# CAN-to-CAN.net
KiCad netlist of a schematic drawn in Altium Designer
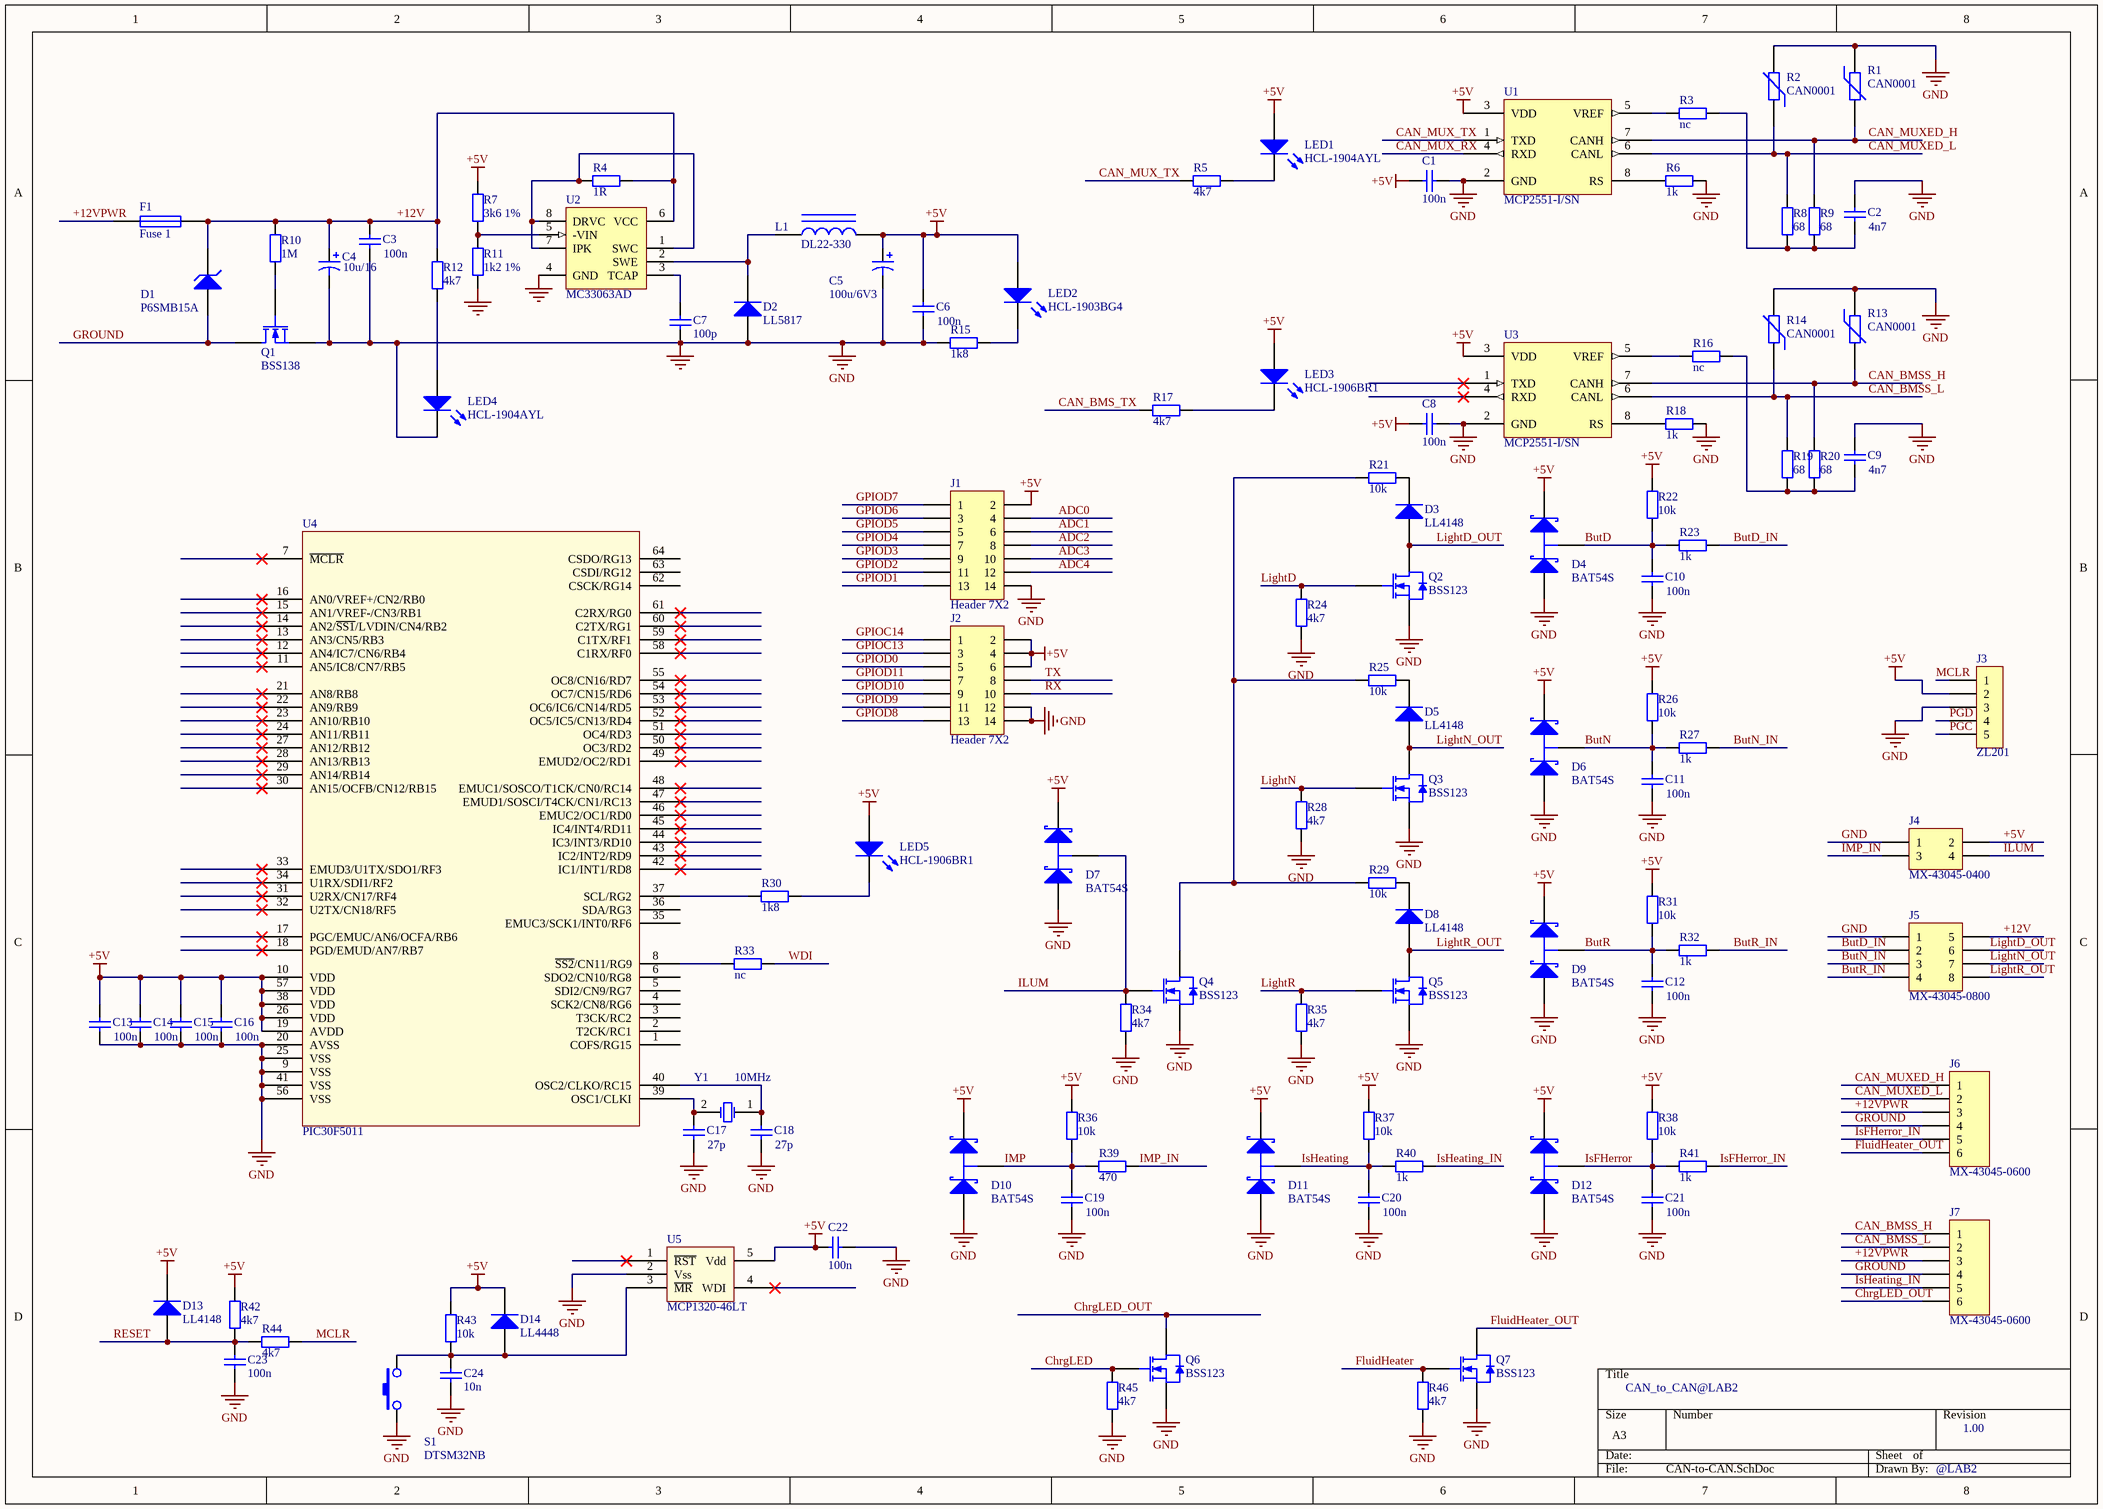
[diagram p0: CAN-to-CAN.SchDoc]

(export (version "E")
  (design (tool "Eeschema 10.0.6"))
  (components
    (comp (ref "C1")
      (value "100n")
      (footprint "0603")
      (description "Capacitor")
      (fields (field (name "PUBLISHER") "Altium Limited"))
      (libsource (lib "Miscellaneous Devices") (part "Cap"))
    )
    (comp (ref "C2")
      (value "4n7")
      (footprint "0603")
      (description "Capacitor")
      (fields (field (name "PUBLISHER") "Altium Limited"))
      (libsource (lib "Miscellaneous Devices") (part "Cap"))
    )
    (comp (ref "C3")
      (value "100n")
      (footprint "0402")
      (description "Capacitor")
      (fields (field (name "PUBLISHER") "Altium Limited"))
      (libsource (lib "Miscellaneous Devices") (part "Cap"))
    )
    (comp (ref "C4")
      (value "10u/16")
      (footprint "0402")
      (description "Polarized Capacitor (Radial)")
      (fields (field (name "PUBLISHER") "Altium Limited"))
      (libsource (lib "Miscellaneous Devices") (part "Cap Pol1"))
    )
    (comp (ref "C5")
      (value "100u/6V3")
      (footprint "0402")
      (description "Polarized Capacitor (Radial)")
      (fields (field (name "PUBLISHER") "Altium Limited"))
      (libsource (lib "Miscellaneous Devices") (part "Cap Pol1"))
    )
    (comp (ref "C6")
      (value "100n")
      (footprint "0603")
      (description "Capacitor")
      (fields (field (name "PUBLISHER") "Altium Limited"))
      (libsource (lib "Miscellaneous Devices") (part "Cap"))
    )
    (comp (ref "C7")
      (value "100p")
      (footprint "0603")
      (description "Capacitor")
      (fields (field (name "PUBLISHER") "Altium Limited"))
      (libsource (lib "Miscellaneous Devices") (part "Cap"))
    )
    (comp (ref "C8")
      (value "100n")
      (footprint "0603")
      (description "Capacitor")
      (fields (field (name "PUBLISHER") "Altium Limited"))
      (libsource (lib "Miscellaneous Devices") (part "Cap"))
    )
    (comp (ref "C9")
      (value "4n7")
      (footprint "0603")
      (description "Capacitor")
      (fields (field (name "PUBLISHER") "Altium Limited"))
      (libsource (lib "Miscellaneous Devices") (part "Cap"))
    )
    (comp (ref "C10")
      (value "100n")
      (footprint "0603")
      (description "Capacitor")
      (fields (field (name "PUBLISHER") "Altium Limited"))
      (libsource (lib "Miscellaneous Devices") (part "Cap"))
    )
    (comp (ref "C11")
      (value "100n")
      (footprint "0603")
      (description "Capacitor")
      (fields (field (name "PUBLISHER") "Altium Limited"))
      (libsource (lib "Miscellaneous Devices") (part "Cap"))
    )
    (comp (ref "C12")
      (value "100n")
      (footprint "0603")
      (description "Capacitor")
      (fields (field (name "PUBLISHER") "Altium Limited"))
      (libsource (lib "Miscellaneous Devices") (part "Cap"))
    )
    (comp (ref "C13")
      (value "100n")
      (footprint "0603")
      (description "Capacitor")
      (fields (field (name "PUBLISHER") "Altium Limited"))
      (libsource (lib "Miscellaneous Devices") (part "Cap"))
    )
    (comp (ref "C14")
      (value "100n")
      (footprint "0603")
      (description "Capacitor")
      (fields (field (name "PUBLISHER") "Altium Limited"))
      (libsource (lib "Miscellaneous Devices") (part "Cap"))
    )
    (comp (ref "C15")
      (value "100n")
      (footprint "0603")
      (description "Capacitor")
      (fields (field (name "PUBLISHER") "Altium Limited"))
      (libsource (lib "Miscellaneous Devices") (part "Cap"))
    )
    (comp (ref "C16")
      (value "100n")
      (footprint "0603")
      (description "Capacitor")
      (fields (field (name "PUBLISHER") "Altium Limited"))
      (libsource (lib "Miscellaneous Devices") (part "Cap"))
    )
    (comp (ref "C17")
      (value "27p")
      (footprint "0603")
      (description "Capacitor")
      (fields (field (name "PUBLISHER") "Altium Limited"))
      (libsource (lib "Miscellaneous Devices") (part "Cap"))
    )
    (comp (ref "C18")
      (value "27p")
      (footprint "0603")
      (description "Capacitor")
      (fields (field (name "PUBLISHER") "Altium Limited"))
      (libsource (lib "Miscellaneous Devices") (part "Cap"))
    )
    (comp (ref "C19")
      (value "100n")
      (footprint "0603")
      (description "Capacitor")
      (fields (field (name "PUBLISHER") "Altium Limited"))
      (libsource (lib "Miscellaneous Devices") (part "Cap"))
    )
    (comp (ref "C20")
      (value "100n")
      (footprint "0603")
      (description "Capacitor")
      (fields (field (name "PUBLISHER") "Altium Limited"))
      (libsource (lib "Miscellaneous Devices") (part "Cap"))
    )
    (comp (ref "C21")
      (value "100n")
      (footprint "0603")
      (description "Capacitor")
      (fields (field (name "PUBLISHER") "Altium Limited"))
      (libsource (lib "Miscellaneous Devices") (part "Cap"))
    )
    (comp (ref "C22")
      (value "100n")
      (footprint "0603")
      (description "Capacitor")
      (fields (field (name "PUBLISHER") "Altium Limited"))
      (libsource (lib "Miscellaneous Devices") (part "Cap"))
    )
    (comp (ref "C23")
      (value "100n")
      (footprint "0603")
      (description "Capacitor")
      (fields (field (name "PUBLISHER") "Altium Limited"))
      (libsource (lib "Miscellaneous Devices") (part "Cap"))
    )
    (comp (ref "C24")
      (value "10n")
      (footprint "0603")
      (description "Capacitor")
      (fields (field (name "PUBLISHER") "Altium Limited"))
      (libsource (lib "Miscellaneous Devices") (part "Cap"))
    )
    (comp (ref "D1")
      (value "P6SMB15A")
      (footprint "SMB")
      (description "Zener Diode")
      (fields (field (name "PUBLISHER") "Altium Limited"))
      (libsource (lib "Miscellaneous Devices") (part "D Zener"))
    )
    (comp (ref "D2")
      (value "LL5817")
      (footprint "DIODE_SMC")
      (description "High Conductance Fast Diode")
      (fields (field (name "PUBLISHER") "Altium Limited"))
      (libsource (lib "FSC Discrete Diode") (part "1N4148"))
    )
    (comp (ref "D3")
      (value "LL4148")
      (footprint "DIODE_SMC")
      (description "High Conductance Fast Diode")
      (fields (field (name "PUBLISHER") "Altium Limited"))
      (libsource (lib "FSC Discrete Diode") (part "1N4148"))
    )
    (comp (ref "D4")
      (value "BAT54S")
      (footprint "SOT-23_M")
      (description "Schottky Barrier Double Diode")
      (fields (field (name "PUBLISHER") "Altium Limited"))
      (libsource (lib "Philips Discrete Diode - Schottky") (part "BAT54S"))
    )
    (comp (ref "D5")
      (value "LL4148")
      (footprint "DIODE_SMC")
      (description "High Conductance Fast Diode")
      (fields (field (name "PUBLISHER") "Altium Limited"))
      (libsource (lib "FSC Discrete Diode") (part "1N4148"))
    )
    (comp (ref "D6")
      (value "BAT54S")
      (footprint "SOT23_M")
      (description "Schottky Barrier Double Diode")
      (fields (field (name "PUBLISHER") "Altium Limited"))
      (libsource (lib "Philips Discrete Diode - Schottky") (part "BAT54S"))
    )
    (comp (ref "D7")
      (value "BAT54S")
      (footprint "SOT23_M")
      (description "Schottky Barrier Double Diode")
      (fields (field (name "PUBLISHER") "Altium Limited"))
      (libsource (lib "Philips Discrete Diode - Schottky") (part "BAT54S"))
    )
    (comp (ref "D8")
      (value "LL4148")
      (footprint "DIODE_SMC")
      (description "High Conductance Fast Diode")
      (fields (field (name "PUBLISHER") "Altium Limited"))
      (libsource (lib "FSC Discrete Diode") (part "1N4148"))
    )
    (comp (ref "D9")
      (value "BAT54S")
      (footprint "SOT23_M")
      (description "Schottky Barrier Double Diode")
      (fields (field (name "PUBLISHER") "Altium Limited"))
      (libsource (lib "Philips Discrete Diode - Schottky") (part "BAT54S"))
    )
    (comp (ref "D10")
      (value "BAT54S")
      (footprint "SOT23_M")
      (description "Schottky Barrier Double Diode")
      (fields (field (name "PUBLISHER") "Altium Limited"))
      (libsource (lib "Philips Discrete Diode - Schottky") (part "BAT54S"))
    )
    (comp (ref "D11")
      (value "BAT54S")
      (footprint "SOT23_M")
      (description "Schottky Barrier Double Diode")
      (fields (field (name "PUBLISHER") "Altium Limited"))
      (libsource (lib "Philips Discrete Diode - Schottky") (part "BAT54S"))
    )
    (comp (ref "D12")
      (value "BAT54S")
      (footprint "SOT23_M")
      (description "Schottky Barrier Double Diode")
      (fields (field (name "PUBLISHER") "Altium Limited"))
      (libsource (lib "Philips Discrete Diode - Schottky") (part "BAT54S"))
    )
    (comp (ref "D13")
      (value "LL4148")
      (footprint "DIODE_SMC")
      (description "High Conductance Fast Diode")
      (fields (field (name "PUBLISHER") "Altium Limited"))
      (libsource (lib "FSC Discrete Diode") (part "1N4148"))
    )
    (comp (ref "D14")
      (value "LL4448")
      (footprint "DIODE_SMC")
      (description "Default Diode")
      (fields (field (name "PUBLISHER") "Altium Limited"))
      (libsource (lib "Miscellaneous Devices") (part "Diode"))
    )
    (comp (ref "F1")
      (value "Fuse 1")
      (footprint "1812")
      (description "Fuse")
      (fields (field (name "PUBLISHER") "Altium Limited"))
      (libsource (lib "Miscellaneous Devices") (part "Fuse 1"))
    )
    (comp (ref "J1")
      (value "Header 7X2")
      (footprint "HDR2X7")
      (description "Header, 7-Pin, Dual row")
      (fields (field (name "PUBLISHER") "Altium Limited"))
      (libsource (lib "Miscellaneous Connectors") (part "Header 7X2"))
    )
    (comp (ref "J2")
      (value "Header 7X2")
      (footprint "HDR2X7")
      (description "Header, 7-Pin, Dual row")
      (fields (field (name "PUBLISHER") "Altium Limited"))
      (libsource (lib "Miscellaneous Connectors") (part "Header 7X2"))
    )
    (comp (ref "J3")
      (value "ZL201")
      (footprint "HDR1X5")
      (description "Connector")
      (libsource (lib "*") (part "CON5"))
    )
    (comp (ref "J4")
      (value "MX-43045-0400")
      (footprint "SOT-343_M")
      (description "Header, 2-Pin, Dual row")
      (fields (field (name "PUBLISHER") "Altium Limited"))
      (libsource (lib "Miscellaneous Connectors") (part "Header 2X2"))
    )
    (comp (ref "J5")
      (value "MX-43045-0800")
      (footprint "DB008_M")
      (description "Header, 4-Pin, Dual row")
      (fields (field (name "PUBLISHER") "Altium Limited"))
      (libsource (lib "Miscellaneous Connectors") (part "Header 4X2A"))
    )
    (comp (ref "J6")
      (value "MX-43045-0600")
      (footprint "Miscellaneous Connectors:HDR1X6")
      (description "Header, 6-Pin")
      (fields (field (name "PUBLISHER") "Altium Limited"))
      (libsource (lib "Miscellaneous Connectors") (part "Header 6"))
    )
    (comp (ref "J7")
      (value "MX-43045-0600")
      (footprint "Miscellaneous Connectors:HDR1X6")
      (description "Header, 6-Pin")
      (fields (field (name "PUBLISHER") "Altium Limited"))
      (libsource (lib "Miscellaneous Connectors") (part "Header 6"))
    )
    (comp (ref "L1")
      (value "DL22-330")
      (footprint "INDC1608L")
      (description "Magnetic-Core Inductor")
      (fields (field (name "PUBLISHER") "Altium Limited"))
      (libsource (lib "Miscellaneous Devices") (part "Inductor Iron"))
    )
    (comp (ref "LED1")
      (value "HCL-1904AYL")
      (footprint "0603")
      (description "Typical BLUE SiC LED")
      (fields (field (name "PUBLISHER") "Altium Limited"))
      (libsource (lib "Miscellaneous Devices") (part "LED3"))
    )
    (comp (ref "LED2")
      (value "HCL-1903BG4")
      (footprint "0603")
      (description "Typical BLUE SiC LED")
      (fields (field (name "PUBLISHER") "Altium Limited"))
      (libsource (lib "Miscellaneous Devices") (part "LED3"))
    )
    (comp (ref "LED3")
      (value "HCL-1906BR1")
      (footprint "0603")
      (description "Typical BLUE SiC LED")
      (fields (field (name "PUBLISHER") "Altium Limited"))
      (libsource (lib "Miscellaneous Devices") (part "LED3"))
    )
    (comp (ref "LED4")
      (value "HCL-1904AYL")
      (footprint "0603")
      (description "Typical BLUE SiC LED")
      (fields (field (name "PUBLISHER") "Altium Limited"))
      (libsource (lib "Miscellaneous Devices") (part "LED3"))
    )
    (comp (ref "LED5")
      (value "HCL-1906BR1")
      (footprint "0603")
      (description "Typical BLUE SiC LED")
      (fields (field (name "PUBLISHER") "Altium Limited"))
      (libsource (lib "Miscellaneous Devices") (part "LED3"))
    )
    (comp (ref "Q1")
      (value "BSS138")
      (footprint "SOT23_M")
      (description "N-Channel Enhancement Mode Vertical DMOS FET")
      (fields (field (name "PUBLISHER") "Altium Limited"))
      (libsource (lib "Zetex Discrete MOSFET") (part "BSS138"))
    )
    (comp (ref "Q2")
      (value "BSS123")
      (footprint "SOT23_M")
      (description "N-channel Enhancement Mode Vertical D-MOSFET")
      (fields (field (name "PUBLISHER") "Altium Limited"))
      (libsource (lib "Philips Discrete MOSFET - Low Power") (part "BSS123"))
    )
    (comp (ref "Q3")
      (value "BSS123")
      (footprint "SOT23_M")
      (description "N-channel Enhancement Mode Vertical D-MOSFET")
      (fields (field (name "PUBLISHER") "Altium Limited"))
      (libsource (lib "Philips Discrete MOSFET - Low Power") (part "BSS123"))
    )
    (comp (ref "Q4")
      (value "BSS123")
      (footprint "SOT23_M")
      (description "N-channel Enhancement Mode Vertical D-MOSFET")
      (fields (field (name "PUBLISHER") "Altium Limited"))
      (libsource (lib "Philips Discrete MOSFET - Low Power") (part "BSS123"))
    )
    (comp (ref "Q5")
      (value "BSS123")
      (footprint "SOT23_M")
      (description "N-channel Enhancement Mode Vertical D-MOSFET")
      (fields (field (name "PUBLISHER") "Altium Limited"))
      (libsource (lib "Philips Discrete MOSFET - Low Power") (part "BSS123"))
    )
    (comp (ref "Q6")
      (value "BSS123")
      (footprint "SOT23_M")
      (description "N-channel Enhancement Mode Vertical D-MOSFET")
      (fields (field (name "PUBLISHER") "Altium Limited"))
      (libsource (lib "Philips Discrete MOSFET - Low Power") (part "BSS123"))
    )
    (comp (ref "Q7")
      (value "BSS123")
      (footprint "SOT23_M")
      (description "N-channel Enhancement Mode Vertical D-MOSFET")
      (fields (field (name "PUBLISHER") "Altium Limited"))
      (libsource (lib "Philips Discrete MOSFET - Low Power") (part "BSS123"))
    )
    (comp (ref "R1")
      (value "CAN0001")
      (footprint "0603")
      (description "Varistor (Voltage-Sensitive Resistor)")
      (fields (field (name "PUBLISHER") "Altium Limited"))
      (libsource (lib "Miscellaneous Devices") (part "Res Varistor"))
    )
    (comp (ref "R2")
      (value "CAN0001")
      (footprint "0603")
      (description "Varistor (Voltage-Sensitive Resistor)")
      (fields (field (name "PUBLISHER") "Altium Limited"))
      (libsource (lib "Miscellaneous Devices") (part "Res Varistor"))
    )
    (comp (ref "R3")
      (value "nc")
      (footprint "0603")
      (description "Resistor")
      (fields (field (name "PUBLISHER") "Altium Limited"))
      (libsource (lib "") (part "Res2_2"))
    )
    (comp (ref "R4")
      (value "1R")
      (footprint "12Z-2010")
      (description "Resistor")
      (fields (field (name "PUBLISHER") "Altium Limited"))
      (libsource (lib "") (part "Res2_2"))
    )
    (comp (ref "R5")
      (value "4k7")
      (footprint "0603")
      (description "Resistor")
      (fields (field (name "PUBLISHER") "Altium Limited"))
      (libsource (lib "") (part "Res2_3"))
    )
    (comp (ref "R6")
      (value "1k")
      (footprint "0603")
      (description "Resistor")
      (fields (field (name "PUBLISHER") "Altium Limited"))
      (libsource (lib "") (part "Res2_2"))
    )
    (comp (ref "R7")
      (value "3k6 1%")
      (footprint "0603")
      (description "Resistor")
      (fields (field (name "PUBLISHER") "Altium Limited"))
      (libsource (lib "") (part "Res2_1"))
    )
    (comp (ref "R8")
      (value "68")
      (footprint "0603")
      (description "Resistor")
      (fields (field (name "PUBLISHER") "Altium Limited"))
      (libsource (lib "") (part "Res2_1"))
    )
    (comp (ref "R9")
      (value "68")
      (footprint "0603")
      (description "Resistor")
      (fields (field (name "PUBLISHER") "Altium Limited"))
      (libsource (lib "") (part "Res2_1"))
    )
    (comp (ref "R10")
      (value "1M")
      (footprint "0603")
      (description "Resistor")
      (fields (field (name "PUBLISHER") "Altium Limited"))
      (libsource (lib "") (part "Res2_1"))
    )
    (comp (ref "R11")
      (value "1k2 1%")
      (footprint "0603")
      (description "Resistor")
      (fields (field (name "PUBLISHER") "Altium Limited"))
      (libsource (lib "Miscellaneous Devices") (part "Res2"))
    )
    (comp (ref "R12")
      (value "4k7")
      (footprint "0603")
      (description "Resistor")
      (fields (field (name "PUBLISHER") "Altium Limited"))
      (libsource (lib "") (part "Res2_1"))
    )
    (comp (ref "R13")
      (value "CAN0001")
      (footprint "0603")
      (description "Varistor (Voltage-Sensitive Resistor)")
      (fields (field (name "PUBLISHER") "Altium Limited"))
      (libsource (lib "Miscellaneous Devices") (part "Res Varistor"))
    )
    (comp (ref "R14")
      (value "CAN0001")
      (footprint "0603")
      (description "Varistor (Voltage-Sensitive Resistor)")
      (fields (field (name "PUBLISHER") "Altium Limited"))
      (libsource (lib "Miscellaneous Devices") (part "Res Varistor"))
    )
    (comp (ref "R15")
      (value "1k8")
      (footprint "0603")
      (description "Resistor")
      (fields (field (name "PUBLISHER") "Altium Limited"))
      (libsource (lib "") (part "Res2_3"))
    )
    (comp (ref "R16")
      (value "nc")
      (footprint "0603")
      (description "Resistor")
      (fields (field (name "PUBLISHER") "Altium Limited"))
      (libsource (lib "") (part "Res2_2"))
    )
    (comp (ref "R17")
      (value "4k7")
      (footprint "0603")
      (description "Resistor")
      (fields (field (name "PUBLISHER") "Altium Limited"))
      (libsource (lib "") (part "Res2_3"))
    )
    (comp (ref "R18")
      (value "1k")
      (footprint "0603")
      (description "Resistor")
      (fields (field (name "PUBLISHER") "Altium Limited"))
      (libsource (lib "") (part "Res2_2"))
    )
    (comp (ref "R19")
      (value "68")
      (footprint "0603")
      (description "Resistor")
      (fields (field (name "PUBLISHER") "Altium Limited"))
      (libsource (lib "") (part "Res2_1"))
    )
    (comp (ref "R20")
      (value "68")
      (footprint "0603")
      (description "Resistor")
      (fields (field (name "PUBLISHER") "Altium Limited"))
      (libsource (lib "") (part "Res2_1"))
    )
    (comp (ref "R21")
      (value "10k")
      (footprint "0603")
      (description "Resistor")
      (fields (field (name "PUBLISHER") "Altium Limited"))
      (libsource (lib "") (part "Res2_2"))
    )
    (comp (ref "R22")
      (value "10k")
      (footprint "0603")
      (description "Resistor")
      (fields (field (name "PUBLISHER") "Altium Limited"))
      (libsource (lib "") (part "Res2_1"))
    )
    (comp (ref "R23")
      (value "1k")
      (footprint "0603")
      (description "Resistor")
      (fields (field (name "PUBLISHER") "Altium Limited"))
      (libsource (lib "") (part "Res2_3"))
    )
    (comp (ref "R24")
      (value "4k7")
      (footprint "0603")
      (description "Resistor")
      (fields (field (name "PUBLISHER") "Altium Limited"))
      (libsource (lib "") (part "Res2_1"))
    )
    (comp (ref "R25")
      (value "10k")
      (footprint "0603")
      (description "Resistor")
      (fields (field (name "PUBLISHER") "Altium Limited"))
      (libsource (lib "") (part "Res2_2"))
    )
    (comp (ref "R26")
      (value "10k")
      (footprint "0603")
      (description "Resistor")
      (fields (field (name "PUBLISHER") "Altium Limited"))
      (libsource (lib "") (part "Res2_1"))
    )
    (comp (ref "R27")
      (value "1k")
      (footprint "0603")
      (description "Resistor")
      (fields (field (name "PUBLISHER") "Altium Limited"))
      (libsource (lib "") (part "Res2_3"))
    )
    (comp (ref "R28")
      (value "4k7")
      (footprint "0603")
      (description "Resistor")
      (fields (field (name "PUBLISHER") "Altium Limited"))
      (libsource (lib "") (part "Res2_1"))
    )
    (comp (ref "R29")
      (value "10k")
      (footprint "0603")
      (description "Resistor")
      (fields (field (name "PUBLISHER") "Altium Limited"))
      (libsource (lib "") (part "Res2_2"))
    )
    (comp (ref "R30")
      (value "1k8")
      (footprint "0603")
      (description "Resistor")
      (fields (field (name "PUBLISHER") "Altium Limited"))
      (libsource (lib "") (part "Res2_3"))
    )
    (comp (ref "R31")
      (value "10k")
      (footprint "0603")
      (description "Resistor")
      (fields (field (name "PUBLISHER") "Altium Limited"))
      (libsource (lib "") (part "Res2_1"))
    )
    (comp (ref "R32")
      (value "1k")
      (footprint "0603")
      (description "Resistor")
      (fields (field (name "PUBLISHER") "Altium Limited"))
      (libsource (lib "") (part "Res2_3"))
    )
    (comp (ref "R33")
      (value "nc")
      (footprint "0603")
      (description "Resistor")
      (fields (field (name "PUBLISHER") "Altium Limited"))
      (libsource (lib "") (part "Res2_3"))
    )
    (comp (ref "R34")
      (value "4k7")
      (footprint "0603")
      (description "Resistor")
      (fields (field (name "PUBLISHER") "Altium Limited"))
      (libsource (lib "") (part "Res2_1"))
    )
    (comp (ref "R35")
      (value "4k7")
      (footprint "0603")
      (description "Resistor")
      (fields (field (name "PUBLISHER") "Altium Limited"))
      (libsource (lib "") (part "Res2_1"))
    )
    (comp (ref "R36")
      (value "10k")
      (footprint "0603")
      (description "Resistor")
      (fields (field (name "PUBLISHER") "Altium Limited"))
      (libsource (lib "") (part "Res2_1"))
    )
    (comp (ref "R37")
      (value "10k")
      (footprint "0603")
      (description "Resistor")
      (fields (field (name "PUBLISHER") "Altium Limited"))
      (libsource (lib "") (part "Res2_1"))
    )
    (comp (ref "R38")
      (value "10k")
      (footprint "0603")
      (description "Resistor")
      (fields (field (name "PUBLISHER") "Altium Limited"))
      (libsource (lib "") (part "Res2_1"))
    )
    (comp (ref "R39")
      (value "470")
      (footprint "0603")
      (description "Resistor")
      (fields (field (name "PUBLISHER") "Altium Limited"))
      (libsource (lib "") (part "Res2_3"))
    )
    (comp (ref "R40")
      (value "1k")
      (footprint "0603")
      (description "Resistor")
      (fields (field (name "PUBLISHER") "Altium Limited"))
      (libsource (lib "") (part "Res2_3"))
    )
    (comp (ref "R41")
      (value "1k")
      (footprint "0603")
      (description "Resistor")
      (fields (field (name "PUBLISHER") "Altium Limited"))
      (libsource (lib "") (part "Res2_3"))
    )
    (comp (ref "R42")
      (value "4k7")
      (footprint "0603")
      (description "Resistor")
      (fields (field (name "PUBLISHER") "Altium Limited"))
      (libsource (lib "") (part "Res2_1"))
    )
    (comp (ref "R43")
      (value "10k")
      (footprint "0603")
      (description "Resistor")
      (fields (field (name "PUBLISHER") "Altium Limited"))
      (libsource (lib "Miscellaneous Devices") (part "Res2"))
    )
    (comp (ref "R44")
      (value "4k7")
      (footprint "0603")
      (description "Resistor")
      (fields (field (name "PUBLISHER") "Altium Limited"))
      (libsource (lib "") (part "Res2_3"))
    )
    (comp (ref "R45")
      (value "4k7")
      (footprint "0603")
      (description "Resistor")
      (fields (field (name "PUBLISHER") "Altium Limited"))
      (libsource (lib "") (part "Res2_1"))
    )
    (comp (ref "R46")
      (value "4k7")
      (footprint "0603")
      (description "Resistor")
      (fields (field (name "PUBLISHER") "Altium Limited"))
      (libsource (lib "") (part "Res2_1"))
    )
    (comp (ref "S1")
      (value "DTSM32NB")
      (footprint "SPST-2")
      (description "Switch PushButton")
      (libsource (lib "*") (part "PUSHB"))
    )
    (comp (ref "U1")
      (value "MCP2551-I/SN")
      (footprint "DB008_M")
      (description "High Speed CAN Transceiver, 8-Pin Plastic SOIC, Industrial Grade")
      (fields (field (name "PUBLISHER") "Altium Limited"))
      (libsource (lib "Microchip Interface Line Transceiver") (part "MCP2551-I/SN"))
    )
    (comp (ref "U2")
      (value "MC33063AD")
      (footprint "SO8_N")
      (description "DC-to-DC Converter Control Circuit")
      (fields (field (name "PUBLISHER") "Altium Limited"))
      (libsource (lib "Motorola Power Mgt DC-DC Converter") (part "MC33063AD"))
    )
    (comp (ref "U3")
      (value "MCP2551-I/SN")
      (footprint "SO8_N")
      (description "High Speed CAN Transceiver, 8-Pin Plastic SOIC, Industrial Grade")
      (fields (field (name "PUBLISHER") "Altium Limited"))
      (libsource (lib "Microchip Interface Line Transceiver") (part "MCP2551-I/SN"))
    )
    (comp (ref "U4")
      (value "PIC30F5011")
      (footprint "ST-64-2_M")
      (description "PIC30F5011 - Up")
      (libsource (lib "X-Tro's Misc") (part "PIC30F5011"))
    )
    (comp (ref "U5")
      (value "MCP1320-46LT")
      (footprint "SOT23-5")
      (libsource (lib "X-Tro's Misc") (part "MCP1320"))
    )
    (comp (ref "Y1")
      (value "10MHz")
      (footprint "XTALSMD2")
      (description "Crystal Oscillator")
      (fields (field (name "PUBLISHER") "Altium Limited"))
      (libsource (lib "Miscellaneous Devices") (part "XTAL"))
    )
  )
  (nets
    (net (code "1") (name "+5V") (class "Default")
      (node (ref "C1") (pin "1") (pinfunction "1_1") (pintype "passive"))
      (node (ref "C13") (pin "1") (pinfunction "1_1") (pintype "passive"))
      (node (ref "C14") (pin "1") (pinfunction "1_1") (pintype "passive"))
      (node (ref "C15") (pin "1") (pinfunction "1_1") (pintype "passive"))
      (node (ref "C16") (pin "1") (pinfunction "1_1") (pintype "passive"))
      (node (ref "C22") (pin "1") (pinfunction "1_1") (pintype "passive"))
      (node (ref "C5") (pin "1") (pinfunction "1_1") (pintype "passive"))
      (node (ref "C6") (pin "1") (pinfunction "1_1") (pintype "passive"))
      (node (ref "C8") (pin "1") (pinfunction "1_1") (pintype "passive"))
      (node (ref "D10") (pin "2") (pinfunction "K_2") (pintype "passive"))
      (node (ref "D11") (pin "2") (pinfunction "K_2") (pintype "passive"))
      (node (ref "D12") (pin "2") (pinfunction "K_2") (pintype "passive"))
      (node (ref "D13") (pin "2") (pinfunction "K_2") (pintype "passive"))
      (node (ref "D14") (pin "2") (pinfunction "K_2") (pintype "passive"))
      (node (ref "D4") (pin "2") (pinfunction "K_2") (pintype "passive"))
      (node (ref "D6") (pin "2") (pinfunction "K_2") (pintype "passive"))
      (node (ref "D7") (pin "2") (pinfunction "K_2") (pintype "passive"))
      (node (ref "D9") (pin "2") (pinfunction "K_2") (pintype "passive"))
      (node (ref "J1") (pin "2") (pinfunction "2_2") (pintype "passive"))
      (node (ref "J2") (pin "2") (pinfunction "2_2") (pintype "passive"))
      (node (ref "J2") (pin "4") (pinfunction "4_4") (pintype "passive"))
      (node (ref "J2") (pin "6") (pinfunction "6_6") (pintype "passive"))
      (node (ref "J3") (pin "2") (pinfunction "2_2") (pintype "passive"))
      (node (ref "J4") (pin "2") (pinfunction "2_2") (pintype "passive"))
      (node (ref "L1") (pin "2") (pinfunction "2_2") (pintype "passive"))
      (node (ref "LED1") (pin "1") (pinfunction "A_1") (pintype "passive"))
      (node (ref "LED2") (pin "1") (pinfunction "A_1") (pintype "passive"))
      (node (ref "LED3") (pin "1") (pinfunction "A_1") (pintype "passive"))
      (node (ref "LED5") (pin "1") (pinfunction "A_1") (pintype "passive"))
      (node (ref "R22") (pin "1") (pinfunction "1_1") (pintype "passive"))
      (node (ref "R26") (pin "1") (pinfunction "1_1") (pintype "passive"))
      (node (ref "R31") (pin "1") (pinfunction "1_1") (pintype "passive"))
      (node (ref "R36") (pin "1") (pinfunction "1_1") (pintype "passive"))
      (node (ref "R37") (pin "1") (pinfunction "1_1") (pintype "passive"))
      (node (ref "R38") (pin "1") (pinfunction "1_1") (pintype "passive"))
      (node (ref "R42") (pin "1") (pinfunction "1_1") (pintype "passive"))
      (node (ref "R43") (pin "2") (pinfunction "2_2") (pintype "passive"))
      (node (ref "R7") (pin "1") (pinfunction "1_1") (pintype "passive"))
      (node (ref "U1") (pin "3") (pinfunction "VDD_3") (pintype "power_in"))
      (node (ref "U3") (pin "3") (pinfunction "VDD_3") (pintype "power_in"))
      (node (ref "U4") (pin "10") (pinfunction "VDD_10") (pintype "passive"))
      (node (ref "U4") (pin "19") (pinfunction "AVDD_19") (pintype "passive"))
      (node (ref "U4") (pin "26") (pinfunction "VDD_26") (pintype "passive"))
      (node (ref "U4") (pin "38") (pinfunction "VDD_38") (pintype "passive"))
      (node (ref "U4") (pin "57") (pinfunction "VDD_57") (pintype "passive"))
      (node (ref "U5") (pin "5") (pinfunction "Vdd_5") (pintype "passive"))
    )
    (net (code "2") (name "/+12V") (class "Default")
      (node (ref "C3") (pin "1") (pinfunction "1_1") (pintype "passive"))
      (node (ref "C4") (pin "1") (pinfunction "1_1") (pintype "passive"))
      (node (ref "D1") (pin "2") (pinfunction "K_2") (pintype "passive"))
      (node (ref "F1") (pin "2") (pinfunction "2_2") (pintype "passive"))
      (node (ref "J5") (pin "5") (pinfunction "5_5") (pintype "passive"))
      (node (ref "R10") (pin "1") (pinfunction "1_1") (pintype "passive"))
      (node (ref "R12") (pin "1") (pinfunction "1_1") (pintype "passive"))
      (node (ref "R4") (pin "2") (pinfunction "2_2") (pintype "passive"))
      (node (ref "U2") (pin "6") (pinfunction "VCC_6") (pintype "power_in"))
    )
    (net (code "3") (name "/+12VPWR") (class "Default")
      (node (ref "F1") (pin "1") (pinfunction "1_1") (pintype "passive"))
      (node (ref "J6") (pin "3") (pinfunction "3_3") (pintype "passive"))
      (node (ref "J7") (pin "3") (pinfunction "3_3") (pintype "passive"))
    )
    (net (code "4") (name "/ADC0") (class "Default")
      (node (ref "J1") (pin "4") (pinfunction "4_4") (pintype "passive"))
    )
    (net (code "5") (name "/ADC1") (class "Default")
      (node (ref "J1") (pin "6") (pinfunction "6_6") (pintype "passive"))
    )
    (net (code "6") (name "/ADC2") (class "Default")
      (node (ref "J1") (pin "8") (pinfunction "8_8") (pintype "passive"))
    )
    (net (code "7") (name "/ADC3") (class "Default")
      (node (ref "J1") (pin "10") (pinfunction "10_10") (pintype "passive"))
    )
    (net (code "8") (name "/ADC4") (class "Default")
      (node (ref "J1") (pin "12") (pinfunction "12_12") (pintype "passive"))
    )
    (net (code "9") (name "/ButD") (class "Default")
      (node (ref "C10") (pin "1") (pinfunction "1_1") (pintype "passive"))
      (node (ref "D4") (pin "3") (pinfunction "C_3") (pintype "passive"))
      (node (ref "R22") (pin "2") (pinfunction "2_2") (pintype "passive"))
      (node (ref "R23") (pin "2") (pinfunction "2_2") (pintype "passive"))
    )
    (net (code "10") (name "/ButD_IN") (class "Default")
      (node (ref "J5") (pin "2") (pinfunction "2_2") (pintype "passive"))
      (node (ref "R23") (pin "1") (pinfunction "1_1") (pintype "passive"))
    )
    (net (code "11") (name "/ButN") (class "Default")
      (node (ref "C11") (pin "1") (pinfunction "1_1") (pintype "passive"))
      (node (ref "D6") (pin "3") (pinfunction "C_3") (pintype "passive"))
      (node (ref "R26") (pin "2") (pinfunction "2_2") (pintype "passive"))
      (node (ref "R27") (pin "2") (pinfunction "2_2") (pintype "passive"))
    )
    (net (code "12") (name "/ButN_IN") (class "Default")
      (node (ref "J5") (pin "3") (pinfunction "3_3") (pintype "passive"))
      (node (ref "R27") (pin "1") (pinfunction "1_1") (pintype "passive"))
    )
    (net (code "13") (name "/ButR") (class "Default")
      (node (ref "C12") (pin "1") (pinfunction "1_1") (pintype "passive"))
      (node (ref "D9") (pin "3") (pinfunction "C_3") (pintype "passive"))
      (node (ref "R31") (pin "2") (pinfunction "2_2") (pintype "passive"))
      (node (ref "R32") (pin "2") (pinfunction "2_2") (pintype "passive"))
    )
    (net (code "14") (name "/ButR_IN") (class "Default")
      (node (ref "J5") (pin "4") (pinfunction "4_4") (pintype "passive"))
      (node (ref "R32") (pin "1") (pinfunction "1_1") (pintype "passive"))
    )
    (net (code "15") (name "/CAN_BMSS_H") (class "Default")
      (node (ref "J7") (pin "1") (pinfunction "1_1") (pintype "passive"))
      (node (ref "R13") (pin "2") (pinfunction "2_2") (pintype "passive"))
      (node (ref "R20") (pin "1") (pinfunction "1_1") (pintype "passive"))
      (node (ref "U3") (pin "7") (pinfunction "CANH_7") (pintype "output"))
    )
    (net (code "16") (name "/CAN_BMSS_L") (class "Default")
      (node (ref "J7") (pin "2") (pinfunction "2_2") (pintype "passive"))
      (node (ref "R14") (pin "1") (pinfunction "1_1") (pintype "passive"))
      (node (ref "R19") (pin "1") (pinfunction "1_1") (pintype "passive"))
      (node (ref "U3") (pin "6") (pinfunction "CANL_6") (pintype "output"))
    )
    (net (code "17") (name "/CAN_BMS_TX") (class "Default")
      (node (ref "R17") (pin "2") (pinfunction "2_2") (pintype "passive"))
    )
    (net (code "18") (name "/CAN_MUXED_H") (class "Default")
      (node (ref "J6") (pin "1") (pinfunction "1_1") (pintype "passive"))
      (node (ref "R1") (pin "2") (pinfunction "2_2") (pintype "passive"))
      (node (ref "R9") (pin "1") (pinfunction "1_1") (pintype "passive"))
      (node (ref "U1") (pin "7") (pinfunction "CANH_7") (pintype "output"))
    )
    (net (code "19") (name "/CAN_MUXED_L") (class "Default")
      (node (ref "J6") (pin "2") (pinfunction "2_2") (pintype "passive"))
      (node (ref "R2") (pin "1") (pinfunction "1_1") (pintype "passive"))
      (node (ref "R8") (pin "1") (pinfunction "1_1") (pintype "passive"))
      (node (ref "U1") (pin "6") (pinfunction "CANL_6") (pintype "output"))
    )
    (net (code "20") (name "/CAN_MUX_RX") (class "Default")
      (node (ref "U1") (pin "4") (pinfunction "RXD_4") (pintype "output"))
    )
    (net (code "21") (name "/CAN_MUX_TX") (class "Default")
      (node (ref "R5") (pin "2") (pinfunction "2_2") (pintype "passive"))
      (node (ref "U1") (pin "1") (pinfunction "TXD_1") (pintype "input"))
    )
    (net (code "22") (name "/ChrgLED") (class "Default")
      (node (ref "Q6") (pin "3") (pinfunction "G_3") (pintype "passive"))
      (node (ref "R45") (pin "1") (pinfunction "1_1") (pintype "passive"))
    )
    (net (code "23") (name "/ChrgLED_OUT") (class "Default")
      (node (ref "J7") (pin "6") (pinfunction "6_6") (pintype "passive"))
      (node (ref "Q6") (pin "1") (pinfunction "D_1") (pintype "passive"))
    )
    (net (code "24") (name "/FluidHeater") (class "Default")
      (node (ref "Q7") (pin "3") (pinfunction "G_3") (pintype "passive"))
      (node (ref "R46") (pin "1") (pinfunction "1_1") (pintype "passive"))
    )
    (net (code "25") (name "/FluidHeater_OUT") (class "Default")
      (node (ref "J6") (pin "6") (pinfunction "6_6") (pintype "passive"))
      (node (ref "Q7") (pin "1") (pinfunction "D_1") (pintype "passive"))
    )
    (net (code "26") (name "/GPIOC13") (class "Default")
      (node (ref "J2") (pin "3") (pinfunction "3_3") (pintype "passive"))
    )
    (net (code "27") (name "/GPIOC14") (class "Default")
      (node (ref "J2") (pin "1") (pinfunction "1_1") (pintype "passive"))
    )
    (net (code "28") (name "/GPIOD0") (class "Default")
      (node (ref "J2") (pin "5") (pinfunction "5_5") (pintype "passive"))
    )
    (net (code "29") (name "/GPIOD1") (class "Default")
      (node (ref "J1") (pin "13") (pinfunction "13_13") (pintype "passive"))
    )
    (net (code "30") (name "/GPIOD2") (class "Default")
      (node (ref "J1") (pin "11") (pinfunction "11_11") (pintype "passive"))
    )
    (net (code "31") (name "/GPIOD3") (class "Default")
      (node (ref "J1") (pin "9") (pinfunction "9_9") (pintype "passive"))
    )
    (net (code "32") (name "/GPIOD4") (class "Default")
      (node (ref "J1") (pin "7") (pinfunction "7_7") (pintype "passive"))
    )
    (net (code "33") (name "/GPIOD5") (class "Default")
      (node (ref "J1") (pin "5") (pinfunction "5_5") (pintype "passive"))
    )
    (net (code "34") (name "/GPIOD6") (class "Default")
      (node (ref "J1") (pin "3") (pinfunction "3_3") (pintype "passive"))
    )
    (net (code "35") (name "/GPIOD7") (class "Default")
      (node (ref "J1") (pin "1") (pinfunction "1_1") (pintype "passive"))
    )
    (net (code "36") (name "/GPIOD8") (class "Default")
      (node (ref "J2") (pin "13") (pinfunction "13_13") (pintype "passive"))
    )
    (net (code "37") (name "/GPIOD9") (class "Default")
      (node (ref "J2") (pin "11") (pinfunction "11_11") (pintype "passive"))
    )
    (net (code "38") (name "/GPIOD10") (class "Default")
      (node (ref "J2") (pin "9") (pinfunction "9_9") (pintype "passive"))
    )
    (net (code "39") (name "/GPIOD11") (class "Default")
      (node (ref "J2") (pin "7") (pinfunction "7_7") (pintype "passive"))
    )
    (net (code "40") (name "/GROUND") (class "Default")
      (node (ref "D1") (pin "1") (pinfunction "A_1") (pintype "passive"))
      (node (ref "J6") (pin "4") (pinfunction "4_4") (pintype "passive"))
      (node (ref "J7") (pin "4") (pinfunction "4_4") (pintype "passive"))
      (node (ref "Q1") (pin "1") (pinfunction "D_1") (pintype "passive"))
    )
    (net (code "41") (name "/ILUM") (class "Default")
      (node (ref "D7") (pin "3") (pinfunction "C_3") (pintype "passive"))
      (node (ref "J4") (pin "4") (pinfunction "4_4") (pintype "passive"))
      (node (ref "Q4") (pin "3") (pinfunction "G_3") (pintype "passive"))
      (node (ref "R34") (pin "1") (pinfunction "1_1") (pintype "passive"))
    )
    (net (code "42") (name "/IMP") (class "Default")
      (node (ref "C19") (pin "1") (pinfunction "1_1") (pintype "passive"))
      (node (ref "D10") (pin "3") (pinfunction "C_3") (pintype "passive"))
      (node (ref "R36") (pin "2") (pinfunction "2_2") (pintype "passive"))
      (node (ref "R39") (pin "2") (pinfunction "2_2") (pintype "passive"))
    )
    (net (code "43") (name "/IMP_IN") (class "Default")
      (node (ref "J4") (pin "3") (pinfunction "3_3") (pintype "passive"))
      (node (ref "R39") (pin "1") (pinfunction "1_1") (pintype "passive"))
    )
    (net (code "44") (name "/IsFHerror") (class "Default")
      (node (ref "C21") (pin "1") (pinfunction "1_1") (pintype "passive"))
      (node (ref "D12") (pin "3") (pinfunction "C_3") (pintype "passive"))
      (node (ref "R38") (pin "2") (pinfunction "2_2") (pintype "passive"))
      (node (ref "R41") (pin "2") (pinfunction "2_2") (pintype "passive"))
    )
    (net (code "45") (name "/IsFHerror_IN") (class "Default")
      (node (ref "J6") (pin "5") (pinfunction "5_5") (pintype "passive"))
      (node (ref "R41") (pin "1") (pinfunction "1_1") (pintype "passive"))
    )
    (net (code "46") (name "/IsHeating") (class "Default")
      (node (ref "C20") (pin "1") (pinfunction "1_1") (pintype "passive"))
      (node (ref "D11") (pin "3") (pinfunction "C_3") (pintype "passive"))
      (node (ref "R37") (pin "2") (pinfunction "2_2") (pintype "passive"))
      (node (ref "R40") (pin "2") (pinfunction "2_2") (pintype "passive"))
    )
    (net (code "47") (name "/IsHeating_IN") (class "Default")
      (node (ref "J7") (pin "5") (pinfunction "5_5") (pintype "passive"))
      (node (ref "R40") (pin "1") (pinfunction "1_1") (pintype "passive"))
    )
    (net (code "48") (name "/LightD") (class "Default")
      (node (ref "Q2") (pin "3") (pinfunction "G_3") (pintype "passive"))
      (node (ref "R24") (pin "1") (pinfunction "1_1") (pintype "passive"))
    )
    (net (code "49") (name "/LightD_OUT") (class "Default")
      (node (ref "D3") (pin "1") (pinfunction "A_1") (pintype "passive"))
      (node (ref "J5") (pin "6") (pinfunction "6_6") (pintype "passive"))
      (node (ref "Q2") (pin "1") (pinfunction "D_1") (pintype "passive"))
    )
    (net (code "50") (name "/LightN") (class "Default")
      (node (ref "Q3") (pin "3") (pinfunction "G_3") (pintype "passive"))
      (node (ref "R28") (pin "1") (pinfunction "1_1") (pintype "passive"))
    )
    (net (code "51") (name "/LightN_OUT") (class "Default")
      (node (ref "D5") (pin "1") (pinfunction "A_1") (pintype "passive"))
      (node (ref "J5") (pin "7") (pinfunction "7_7") (pintype "passive"))
      (node (ref "Q3") (pin "1") (pinfunction "D_1") (pintype "passive"))
    )
    (net (code "52") (name "/LightR") (class "Default")
      (node (ref "Q5") (pin "3") (pinfunction "G_3") (pintype "passive"))
      (node (ref "R35") (pin "1") (pinfunction "1_1") (pintype "passive"))
    )
    (net (code "53") (name "/LightR_OUT") (class "Default")
      (node (ref "D8") (pin "1") (pinfunction "A_1") (pintype "passive"))
      (node (ref "J5") (pin "8") (pinfunction "8_8") (pintype "passive"))
      (node (ref "Q5") (pin "1") (pinfunction "D_1") (pintype "passive"))
    )
    (net (code "54") (name "/MCLR") (class "Default")
      (node (ref "J3") (pin "1") (pinfunction "1_1") (pintype "passive"))
      (node (ref "R44") (pin "1") (pinfunction "1_1") (pintype "passive"))
    )
    (net (code "55") (name "/PGC") (class "Default")
      (node (ref "J3") (pin "5") (pinfunction "5_5") (pintype "passive"))
    )
    (net (code "56") (name "/PGD") (class "Default")
      (node (ref "J3") (pin "4") (pinfunction "4_4") (pintype "passive"))
    )
    (net (code "57") (name "/RESET") (class "Default")
      (node (ref "C23") (pin "2") (pinfunction "2_2") (pintype "passive"))
      (node (ref "D13") (pin "1") (pinfunction "A_1") (pintype "passive"))
      (node (ref "R42") (pin "2") (pinfunction "2_2") (pintype "passive"))
      (node (ref "R44") (pin "2") (pinfunction "2_2") (pintype "passive"))
    )
    (net (code "58") (name "/RX") (class "Default")
      (node (ref "J2") (pin "10") (pinfunction "10_10") (pintype "passive"))
    )
    (net (code "59") (name "/TX") (class "Default")
      (node (ref "J2") (pin "8") (pinfunction "8_8") (pintype "passive"))
    )
    (net (code "60") (name "/WDI") (class "Default")
      (node (ref "R33") (pin "1") (pinfunction "1_1") (pintype "passive"))
    )
    (net (code "61") (name "GND") (class "Default")
      (node (ref "C1") (pin "2") (pinfunction "2_2") (pintype "passive"))
      (node (ref "C10") (pin "2") (pinfunction "2_2") (pintype "passive"))
      (node (ref "C11") (pin "2") (pinfunction "2_2") (pintype "passive"))
      (node (ref "C12") (pin "2") (pinfunction "2_2") (pintype "passive"))
      (node (ref "C13") (pin "2") (pinfunction "2_2") (pintype "passive"))
      (node (ref "C14") (pin "2") (pinfunction "2_2") (pintype "passive"))
      (node (ref "C15") (pin "2") (pinfunction "2_2") (pintype "passive"))
      (node (ref "C16") (pin "2") (pinfunction "2_2") (pintype "passive"))
      (node (ref "C17") (pin "2") (pinfunction "2_2") (pintype "passive"))
      (node (ref "C18") (pin "2") (pinfunction "2_2") (pintype "passive"))
      (node (ref "C19") (pin "2") (pinfunction "2_2") (pintype "passive"))
      (node (ref "C2") (pin "1") (pinfunction "1_1") (pintype "passive"))
      (node (ref "C20") (pin "2") (pinfunction "2_2") (pintype "passive"))
      (node (ref "C21") (pin "2") (pinfunction "2_2") (pintype "passive"))
      (node (ref "C22") (pin "2") (pinfunction "2_2") (pintype "passive"))
      (node (ref "C23") (pin "1") (pinfunction "1_1") (pintype "passive"))
      (node (ref "C24") (pin "1") (pinfunction "1_1") (pintype "passive"))
      (node (ref "C3") (pin "2") (pinfunction "2_2") (pintype "passive"))
      (node (ref "C4") (pin "2") (pinfunction "2_2") (pintype "passive"))
      (node (ref "C5") (pin "2") (pinfunction "2_2") (pintype "passive"))
      (node (ref "C6") (pin "2") (pinfunction "2_2") (pintype "passive"))
      (node (ref "C7") (pin "1") (pinfunction "1_1") (pintype "passive"))
      (node (ref "C8") (pin "2") (pinfunction "2_2") (pintype "passive"))
      (node (ref "C9") (pin "1") (pinfunction "1_1") (pintype "passive"))
      (node (ref "D10") (pin "1") (pinfunction "A_1") (pintype "passive"))
      (node (ref "D11") (pin "1") (pinfunction "A_1") (pintype "passive"))
      (node (ref "D12") (pin "1") (pinfunction "A_1") (pintype "passive"))
      (node (ref "D2") (pin "1") (pinfunction "A_1") (pintype "passive"))
      (node (ref "D4") (pin "1") (pinfunction "A_1") (pintype "passive"))
      (node (ref "D6") (pin "1") (pinfunction "A_1") (pintype "passive"))
      (node (ref "D7") (pin "1") (pinfunction "A_1") (pintype "passive"))
      (node (ref "D9") (pin "1") (pinfunction "A_1") (pintype "passive"))
      (node (ref "J1") (pin "14") (pinfunction "14_14") (pintype "passive"))
      (node (ref "J2") (pin "12") (pinfunction "12_12") (pintype "passive"))
      (node (ref "J2") (pin "14") (pinfunction "14_14") (pintype "passive"))
      (node (ref "J3") (pin "3") (pinfunction "3_3") (pintype "passive"))
      (node (ref "J4") (pin "1") (pinfunction "1_1") (pintype "passive"))
      (node (ref "J5") (pin "1") (pinfunction "1_1") (pintype "passive"))
      (node (ref "LED4") (pin "2") (pinfunction "K_2") (pintype "passive"))
      (node (ref "Q1") (pin "2") (pinfunction "S_2") (pintype "passive"))
      (node (ref "Q2") (pin "2") (pinfunction "S_2") (pintype "passive"))
      (node (ref "Q3") (pin "2") (pinfunction "S_2") (pintype "passive"))
      (node (ref "Q4") (pin "2") (pinfunction "S_2") (pintype "passive"))
      (node (ref "Q5") (pin "2") (pinfunction "S_2") (pintype "passive"))
      (node (ref "Q6") (pin "2") (pinfunction "S_2") (pintype "passive"))
      (node (ref "Q7") (pin "2") (pinfunction "S_2") (pintype "passive"))
      (node (ref "R1") (pin "1") (pinfunction "1_1") (pintype "passive"))
      (node (ref "R11") (pin "1") (pinfunction "1_1") (pintype "passive"))
      (node (ref "R13") (pin "1") (pinfunction "1_1") (pintype "passive"))
      (node (ref "R14") (pin "2") (pinfunction "2_2") (pintype "passive"))
      (node (ref "R15") (pin "2") (pinfunction "2_2") (pintype "passive"))
      (node (ref "R18") (pin "2") (pinfunction "2_2") (pintype "passive"))
      (node (ref "R2") (pin "2") (pinfunction "2_2") (pintype "passive"))
      (node (ref "R24") (pin "2") (pinfunction "2_2") (pintype "passive"))
      (node (ref "R28") (pin "2") (pinfunction "2_2") (pintype "passive"))
      (node (ref "R34") (pin "2") (pinfunction "2_2") (pintype "passive"))
      (node (ref "R35") (pin "2") (pinfunction "2_2") (pintype "passive"))
      (node (ref "R45") (pin "2") (pinfunction "2_2") (pintype "passive"))
      (node (ref "R46") (pin "2") (pinfunction "2_2") (pintype "passive"))
      (node (ref "R6") (pin "2") (pinfunction "2_2") (pintype "passive"))
      (node (ref "S1") (pin "1") (pintype "passive"))
      (node (ref "U1") (pin "2") (pinfunction "GND_2") (pintype "power_in"))
      (node (ref "U2") (pin "4") (pinfunction "GND_4") (pintype "power_in"))
      (node (ref "U3") (pin "2") (pinfunction "GND_2") (pintype "power_in"))
      (node (ref "U4") (pin "20") (pinfunction "AVSS_20") (pintype "passive"))
      (node (ref "U4") (pin "25") (pinfunction "VSS_25") (pintype "passive"))
      (node (ref "U4") (pin "41") (pinfunction "VSS_41") (pintype "passive"))
      (node (ref "U4") (pin "56") (pinfunction "VSS_56") (pintype "passive"))
      (node (ref "U4") (pin "9") (pinfunction "VSS_9") (pintype "passive"))
      (node (ref "U5") (pin "2") (pinfunction "Vss_2") (pintype "passive"))
    )
    (net (code "62") (name "Net-(C2-Pad2)") (class "Default")
      (node (ref "C2") (pin "2") (pinfunction "2_2") (pintype "passive"))
      (node (ref "R3") (pin "2") (pinfunction "2_2") (pintype "passive"))
      (node (ref "R8") (pin "2") (pinfunction "2_2") (pintype "passive"))
      (node (ref "R9") (pin "2") (pinfunction "2_2") (pintype "passive"))
    )
    (net (code "63") (name "Net-(C9-Pad2)") (class "Default")
      (node (ref "C9") (pin "2") (pinfunction "2_2") (pintype "passive"))
      (node (ref "R16") (pin "2") (pinfunction "2_2") (pintype "passive"))
      (node (ref "R19") (pin "2") (pinfunction "2_2") (pintype "passive"))
      (node (ref "R20") (pin "2") (pinfunction "2_2") (pintype "passive"))
    )
    (net (code "64") (name "Net-(D2-K)") (class "Default")
      (node (ref "D2") (pin "2") (pinfunction "K_2") (pintype "passive"))
      (node (ref "L1") (pin "1") (pinfunction "1_1") (pintype "passive"))
      (node (ref "U2") (pin "2") (pinfunction "SWE_2") (pintype "open_emitter"))
    )
    (net (code "65") (name "Net-(D3-K)") (class "Default")
      (node (ref "D3") (pin "2") (pinfunction "K_2") (pintype "passive"))
      (node (ref "R21") (pin "2") (pinfunction "2_2") (pintype "passive"))
    )
    (net (code "66") (name "Net-(D5-K)") (class "Default")
      (node (ref "D5") (pin "2") (pinfunction "K_2") (pintype "passive"))
      (node (ref "R25") (pin "2") (pinfunction "2_2") (pintype "passive"))
    )
    (net (code "67") (name "Net-(D8-K)") (class "Default")
      (node (ref "D8") (pin "2") (pinfunction "K_2") (pintype "passive"))
      (node (ref "R29") (pin "2") (pinfunction "2_2") (pintype "passive"))
    )
    (net (code "68") (name "Net-(D14-A)") (class "Default")
      (node (ref "C24") (pin "2") (pinfunction "2_2") (pintype "passive"))
      (node (ref "D14") (pin "1") (pinfunction "A_1") (pintype "passive"))
      (node (ref "R43") (pin "1") (pinfunction "1_1") (pintype "passive"))
      (node (ref "S1") (pin "2") (pintype "passive"))
      (node (ref "U5") (pin "3") (pinfunction "~{MR}_3") (pintype "passive"))
    )
    (net (code "69") (name "Net-(LED1-K)") (class "Default")
      (node (ref "LED1") (pin "2") (pinfunction "K_2") (pintype "passive"))
      (node (ref "R5") (pin "1") (pinfunction "1_1") (pintype "passive"))
    )
    (net (code "70") (name "Net-(LED2-K)") (class "Default")
      (node (ref "LED2") (pin "2") (pinfunction "K_2") (pintype "passive"))
      (node (ref "R15") (pin "1") (pinfunction "1_1") (pintype "passive"))
    )
    (net (code "71") (name "Net-(LED3-K)") (class "Default")
      (node (ref "LED3") (pin "2") (pinfunction "K_2") (pintype "passive"))
      (node (ref "R17") (pin "1") (pinfunction "1_1") (pintype "passive"))
    )
    (net (code "72") (name "Net-(LED4-A)") (class "Default")
      (node (ref "LED4") (pin "1") (pinfunction "A_1") (pintype "passive"))
      (node (ref "R12") (pin "2") (pinfunction "2_2") (pintype "passive"))
    )
    (net (code "73") (name "Net-(LED5-K)") (class "Default")
      (node (ref "LED5") (pin "2") (pinfunction "K_2") (pintype "passive"))
      (node (ref "R30") (pin "1") (pinfunction "1_1") (pintype "passive"))
    )
    (net (code "74") (name "Net-(Q1-G)") (class "Default")
      (node (ref "Q1") (pin "3") (pinfunction "G_3") (pintype "passive"))
      (node (ref "R10") (pin "2") (pinfunction "2_2") (pintype "passive"))
    )
    (net (code "75") (name "Net-(Q4-D)") (class "Default")
      (node (ref "Q4") (pin "1") (pinfunction "D_1") (pintype "passive"))
      (node (ref "R21") (pin "1") (pinfunction "1_1") (pintype "passive"))
      (node (ref "R25") (pin "1") (pinfunction "1_1") (pintype "passive"))
      (node (ref "R29") (pin "1") (pinfunction "1_1") (pintype "passive"))
    )
    (net (code "76") (name "Net-(U1-RS)") (class "Default")
      (node (ref "R6") (pin "1") (pinfunction "1_1") (pintype "passive"))
      (node (ref "U1") (pin "8") (pinfunction "RS_8") (pintype "passive"))
    )
    (net (code "77") (name "Net-(U1-VREF)") (class "Default")
      (node (ref "R3") (pin "1") (pinfunction "1_1") (pintype "passive"))
      (node (ref "U1") (pin "5") (pinfunction "VREF_5") (pintype "output"))
    )
    (net (code "78") (name "Net-(U2--VIN)") (class "Default")
      (node (ref "R11") (pin "2") (pinfunction "2_2") (pintype "passive"))
      (node (ref "R7") (pin "2") (pinfunction "2_2") (pintype "passive"))
      (node (ref "U2") (pin "5") (pinfunction "-VIN_5") (pintype "input"))
    )
    (net (code "79") (name "Net-(U2-DRVC)") (class "Default")
      (node (ref "R4") (pin "1") (pinfunction "1_1") (pintype "passive"))
      (node (ref "U2") (pin "1") (pinfunction "SWC_1") (pintype "open_collector"))
      (node (ref "U2") (pin "7") (pinfunction "IPK_7") (pintype "passive"))
      (node (ref "U2") (pin "8") (pinfunction "DRVC_8") (pintype "open_collector"))
    )
    (net (code "80") (name "Net-(U2-TCAP)") (class "Default")
      (node (ref "C7") (pin "2") (pinfunction "2_2") (pintype "passive"))
      (node (ref "U2") (pin "3") (pinfunction "TCAP_3") (pintype "passive"))
    )
    (net (code "81") (name "Net-(U3-RS)") (class "Default")
      (node (ref "R18") (pin "1") (pinfunction "1_1") (pintype "passive"))
      (node (ref "U3") (pin "8") (pinfunction "RS_8") (pintype "passive"))
    )
    (net (code "82") (name "Net-(U3-VREF)") (class "Default")
      (node (ref "R16") (pin "1") (pinfunction "1_1") (pintype "passive"))
      (node (ref "U3") (pin "5") (pinfunction "VREF_5") (pintype "output"))
    )
    (net (code "83") (name "Net-(U4-OSC1{slash}CLKI)") (class "Default")
      (node (ref "C17") (pin "1") (pinfunction "1_1") (pintype "passive"))
      (node (ref "U4") (pin "39") (pinfunction "OSC1/CLKI_39") (pintype "passive"))
      (node (ref "Y1") (pin "2") (pinfunction "OSC2_2") (pintype "passive"))
    )
    (net (code "84") (name "Net-(U4-OSC2{slash}CLKO{slash}RC15)") (class "Default")
      (node (ref "C18") (pin "1") (pinfunction "1_1") (pintype "passive"))
      (node (ref "U4") (pin "40") (pinfunction "OSC2/CLKO/RC15_40") (pintype "passive"))
      (node (ref "Y1") (pin "1") (pinfunction "OSC1_1") (pintype "passive"))
    )
    (net (code "85") (name "Net-(U4-SCL{slash}RG2)") (class "Default")
      (node (ref "R30") (pin "2") (pinfunction "2_2") (pintype "passive"))
      (node (ref "U4") (pin "37") (pinfunction "SCL/RG2_37") (pintype "passive"))
    )
    (net (code "86") (name "Net-(U4-~{SS2}{slash}CN11{slash}RG9)") (class "Default")
      (node (ref "R33") (pin "2") (pinfunction "2_2") (pintype "passive"))
      (node (ref "U4") (pin "8") (pinfunction "~{SS2}/CN11/RG9_8") (pintype "passive"))
    )
    (net (code "87") (name "unconnected-(U3-RXD-Pad4)") (class "Default")
      (node (ref "U3") (pin "4") (pinfunction "RXD_4") (pintype "output+no_connect"))
    )
    (net (code "88") (name "unconnected-(U3-TXD-Pad1)") (class "Default")
      (node (ref "U3") (pin "1") (pinfunction "TXD_1") (pintype "input+no_connect"))
    )
    (net (code "89") (name "unconnected-(U4-AN0{slash}VREF+{slash}CN2{slash}RB0-Pad16)") (class "Default")
      (node (ref "U4") (pin "16") (pinfunction "AN0/VREF+/CN2/RB0_16") (pintype "passive+no_connect"))
    )
    (net (code "90") (name "unconnected-(U4-AN1{slash}VREF-{slash}CN3{slash}RB1-Pad15)") (class "Default")
      (node (ref "U4") (pin "15") (pinfunction "AN1/VREF-/CN3/RB1_15") (pintype "passive+no_connect"))
    )
    (net (code "91") (name "unconnected-(U4-AN2{slash}~{SS1}{slash}LVDIN{slash}CN4{slash}RB2-Pad14)") (class "Default")
      (node (ref "U4") (pin "14") (pinfunction "AN2/~{SS1}/LVDIN/CN4/RB2_14") (pintype "passive+no_connect"))
    )
    (net (code "92") (name "unconnected-(U4-AN3{slash}CN5{slash}RB3-Pad13)") (class "Default")
      (node (ref "U4") (pin "13") (pinfunction "AN3/CN5/RB3_13") (pintype "passive+no_connect"))
    )
    (net (code "93") (name "unconnected-(U4-AN4{slash}IC7{slash}CN6{slash}RB4-Pad12)") (class "Default")
      (node (ref "U4") (pin "12") (pinfunction "AN4/IC7/CN6/RB4_12") (pintype "passive+no_connect"))
    )
    (net (code "94") (name "unconnected-(U4-AN5{slash}IC8{slash}CN7{slash}RB5-Pad11)") (class "Default")
      (node (ref "U4") (pin "11") (pinfunction "AN5/IC8/CN7/RB5_11") (pintype "passive+no_connect"))
    )
    (net (code "95") (name "unconnected-(U4-AN8{slash}RB8-Pad21)") (class "Default")
      (node (ref "U4") (pin "21") (pinfunction "AN8/RB8_21") (pintype "passive+no_connect"))
    )
    (net (code "96") (name "unconnected-(U4-AN9{slash}RB9-Pad22)") (class "Default")
      (node (ref "U4") (pin "22") (pinfunction "AN9/RB9_22") (pintype "passive+no_connect"))
    )
    (net (code "97") (name "unconnected-(U4-AN10{slash}RB10-Pad23)") (class "Default")
      (node (ref "U4") (pin "23") (pinfunction "AN10/RB10_23") (pintype "passive+no_connect"))
    )
    (net (code "98") (name "unconnected-(U4-AN11{slash}RB11-Pad24)") (class "Default")
      (node (ref "U4") (pin "24") (pinfunction "AN11/RB11_24") (pintype "passive+no_connect"))
    )
    (net (code "99") (name "unconnected-(U4-AN12{slash}RB12-Pad27)") (class "Default")
      (node (ref "U4") (pin "27") (pinfunction "AN12/RB12_27") (pintype "passive+no_connect"))
    )
    (net (code "100") (name "unconnected-(U4-AN13{slash}RB13-Pad28)") (class "Default")
      (node (ref "U4") (pin "28") (pinfunction "AN13/RB13_28") (pintype "passive+no_connect"))
    )
    (net (code "101") (name "unconnected-(U4-AN14{slash}RB14-Pad29)") (class "Default")
      (node (ref "U4") (pin "29") (pinfunction "AN14/RB14_29") (pintype "passive+no_connect"))
    )
    (net (code "102") (name "unconnected-(U4-AN15{slash}OCFB{slash}CN12{slash}RB15-Pad30)") (class "Default")
      (node (ref "U4") (pin "30") (pinfunction "AN15/OCFB/CN12/RB15_30") (pintype "passive+no_connect"))
    )
    (net (code "103") (name "unconnected-(U4-C1RX{slash}RF0-Pad58)") (class "Default")
      (node (ref "U4") (pin "58") (pinfunction "C1RX/RF0_58") (pintype "passive+no_connect"))
    )
    (net (code "104") (name "unconnected-(U4-C1TX{slash}RF1-Pad59)") (class "Default")
      (node (ref "U4") (pin "59") (pinfunction "C1TX/RF1_59") (pintype "passive+no_connect"))
    )
    (net (code "105") (name "unconnected-(U4-C2RX{slash}RG0-Pad61)") (class "Default")
      (node (ref "U4") (pin "61") (pinfunction "C2RX/RG0_61") (pintype "passive+no_connect"))
    )
    (net (code "106") (name "unconnected-(U4-C2TX{slash}RG1-Pad60)") (class "Default")
      (node (ref "U4") (pin "60") (pinfunction "C2TX/RG1_60") (pintype "passive+no_connect"))
    )
    (net (code "107") (name "unconnected-(U4-COFS{slash}RG15-Pad1)") (class "Default")
      (node (ref "U4") (pin "1") (pinfunction "COFS/RG15_1") (pintype "passive"))
    )
    (net (code "108") (name "unconnected-(U4-CSCK{slash}RG14-Pad62)") (class "Default")
      (node (ref "U4") (pin "62") (pinfunction "CSCK/RG14_62") (pintype "passive"))
    )
    (net (code "109") (name "unconnected-(U4-CSDI{slash}RG12-Pad63)") (class "Default")
      (node (ref "U4") (pin "63") (pinfunction "CSDI/RG12_63") (pintype "passive"))
    )
    (net (code "110") (name "unconnected-(U4-CSDO{slash}RG13-Pad64)") (class "Default")
      (node (ref "U4") (pin "64") (pinfunction "CSDO/RG13_64") (pintype "passive"))
    )
    (net (code "111") (name "unconnected-(U4-EMUC1{slash}SOSCO{slash}T1CK{slash}CN0{slash}RC14-Pad48)") (class "Default")
      (node (ref "U4") (pin "48") (pinfunction "EMUC1/SOSCO/T1CK/CN0/RC14_48") (pintype "passive+no_connect"))
    )
    (net (code "112") (name "unconnected-(U4-EMUC2{slash}OC1{slash}RD0-Pad46)") (class "Default")
      (node (ref "U4") (pin "46") (pinfunction "EMUC2/OC1/RD0_46") (pintype "passive+no_connect"))
    )
    (net (code "113") (name "unconnected-(U4-EMUC3{slash}SCK1{slash}INT0{slash}RF6-Pad35)") (class "Default")
      (node (ref "U4") (pin "35") (pinfunction "EMUC3/SCK1/INT0/RF6_35") (pintype "passive"))
    )
    (net (code "114") (name "unconnected-(U4-EMUD1{slash}SOSCI{slash}T4CK{slash}CN1{slash}RC13-Pad47)") (class "Default")
      (node (ref "U4") (pin "47") (pinfunction "EMUD1/SOSCI/T4CK/CN1/RC13_47") (pintype "passive+no_connect"))
    )
    (net (code "115") (name "unconnected-(U4-EMUD2{slash}OC2{slash}RD1-Pad49)") (class "Default")
      (node (ref "U4") (pin "49") (pinfunction "EMUD2/OC2/RD1_49") (pintype "passive+no_connect"))
    )
    (net (code "116") (name "unconnected-(U4-EMUD3{slash}U1TX{slash}SDO1{slash}RF3-Pad33)") (class "Default")
      (node (ref "U4") (pin "33") (pinfunction "EMUD3/U1TX/SDO1/RF3_33") (pintype "passive+no_connect"))
    )
    (net (code "117") (name "unconnected-(U4-IC1{slash}INT1{slash}RD8-Pad42)") (class "Default")
      (node (ref "U4") (pin "42") (pinfunction "IC1/INT1/RD8_42") (pintype "passive+no_connect"))
    )
    (net (code "118") (name "unconnected-(U4-IC2{slash}INT2{slash}RD9-Pad43)") (class "Default")
      (node (ref "U4") (pin "43") (pinfunction "IC2/INT2/RD9_43") (pintype "passive+no_connect"))
    )
    (net (code "119") (name "unconnected-(U4-IC3{slash}INT3{slash}RD10-Pad44)") (class "Default")
      (node (ref "U4") (pin "44") (pinfunction "IC3/INT3/RD10_44") (pintype "passive+no_connect"))
    )
    (net (code "120") (name "unconnected-(U4-IC4{slash}INT4{slash}RD11-Pad45)") (class "Default")
      (node (ref "U4") (pin "45") (pinfunction "IC4/INT4/RD11_45") (pintype "passive+no_connect"))
    )
    (net (code "121") (name "unconnected-(U4-OC3{slash}RD2-Pad50)") (class "Default")
      (node (ref "U4") (pin "50") (pinfunction "OC3/RD2_50") (pintype "passive+no_connect"))
    )
    (net (code "122") (name "unconnected-(U4-OC4{slash}RD3-Pad51)") (class "Default")
      (node (ref "U4") (pin "51") (pinfunction "OC4/RD3_51") (pintype "passive+no_connect"))
    )
    (net (code "123") (name "unconnected-(U4-OC5{slash}IC5{slash}CN13{slash}RD4-Pad52)") (class "Default")
      (node (ref "U4") (pin "52") (pinfunction "OC5/IC5/CN13/RD4_52") (pintype "passive+no_connect"))
    )
    (net (code "124") (name "unconnected-(U4-OC6{slash}IC6{slash}CN14{slash}RD5-Pad53)") (class "Default")
      (node (ref "U4") (pin "53") (pinfunction "OC6/IC6/CN14/RD5_53") (pintype "passive+no_connect"))
    )
    (net (code "125") (name "unconnected-(U4-OC7{slash}CN15{slash}RD6-Pad54)") (class "Default")
      (node (ref "U4") (pin "54") (pinfunction "OC7/CN15/RD6_54") (pintype "passive+no_connect"))
    )
    (net (code "126") (name "unconnected-(U4-OC8{slash}CN16{slash}RD7-Pad55)") (class "Default")
      (node (ref "U4") (pin "55") (pinfunction "OC8/CN16/RD7_55") (pintype "passive+no_connect"))
    )
    (net (code "127") (name "unconnected-(U4-PGC{slash}EMUC{slash}AN6{slash}OCFA{slash}RB6-Pad17)") (class "Default")
      (node (ref "U4") (pin "17") (pinfunction "PGC/EMUC/AN6/OCFA/RB6_17") (pintype "passive+no_connect"))
    )
    (net (code "128") (name "unconnected-(U4-PGD{slash}EMUD{slash}AN7{slash}RB7-Pad18)") (class "Default")
      (node (ref "U4") (pin "18") (pinfunction "PGD/EMUD/AN7/RB7_18") (pintype "passive+no_connect"))
    )
    (net (code "129") (name "unconnected-(U4-SCK2{slash}CN8{slash}RG6-Pad4)") (class "Default")
      (node (ref "U4") (pin "4") (pinfunction "SCK2/CN8/RG6_4") (pintype "passive"))
    )
    (net (code "130") (name "unconnected-(U4-SDA{slash}RG3-Pad36)") (class "Default")
      (node (ref "U4") (pin "36") (pinfunction "SDA/RG3_36") (pintype "passive"))
    )
    (net (code "131") (name "unconnected-(U4-SDI2{slash}CN9{slash}RG7-Pad5)") (class "Default")
      (node (ref "U4") (pin "5") (pinfunction "SDI2/CN9/RG7_5") (pintype "passive"))
    )
    (net (code "132") (name "unconnected-(U4-SDO2{slash}CN10{slash}RG8-Pad6)") (class "Default")
      (node (ref "U4") (pin "6") (pinfunction "SDO2/CN10/RG8_6") (pintype "passive"))
    )
    (net (code "133") (name "unconnected-(U4-T2CK{slash}RC1-Pad2)") (class "Default")
      (node (ref "U4") (pin "2") (pinfunction "T2CK/RC1_2") (pintype "passive"))
    )
    (net (code "134") (name "unconnected-(U4-T3CK{slash}RC2-Pad3)") (class "Default")
      (node (ref "U4") (pin "3") (pinfunction "T3CK/RC2_3") (pintype "passive"))
    )
    (net (code "135") (name "unconnected-(U4-U1RX{slash}SDI1{slash}RF2-Pad34)") (class "Default")
      (node (ref "U4") (pin "34") (pinfunction "U1RX/SDI1/RF2_34") (pintype "passive+no_connect"))
    )
    (net (code "136") (name "unconnected-(U4-U2RX{slash}CN17{slash}RF4-Pad31)") (class "Default")
      (node (ref "U4") (pin "31") (pinfunction "U2RX/CN17/RF4_31") (pintype "passive+no_connect"))
    )
    (net (code "137") (name "unconnected-(U4-U2TX{slash}CN18{slash}RF5-Pad32)") (class "Default")
      (node (ref "U4") (pin "32") (pinfunction "U2TX/CN18/RF5_32") (pintype "passive+no_connect"))
    )
    (net (code "138") (name "unconnected-(U4-~{MCLR}-Pad7)") (class "Default")
      (node (ref "U4") (pin "7") (pinfunction "~{MCLR}_7") (pintype "passive+no_connect"))
    )
    (net (code "139") (name "unconnected-(U5-WDI-Pad4)") (class "Default")
      (node (ref "U5") (pin "4") (pinfunction "WDI_4") (pintype "passive+no_connect"))
    )
    (net (code "140") (name "unconnected-(U5-~{RST}-Pad1)") (class "Default")
      (node (ref "U5") (pin "1") (pinfunction "~{RST}_1") (pintype "passive+no_connect"))
    )
  )
)
